# MezzanineDCDC_4646.net
KiCad netlist of a schematic drawn in Altium Designer
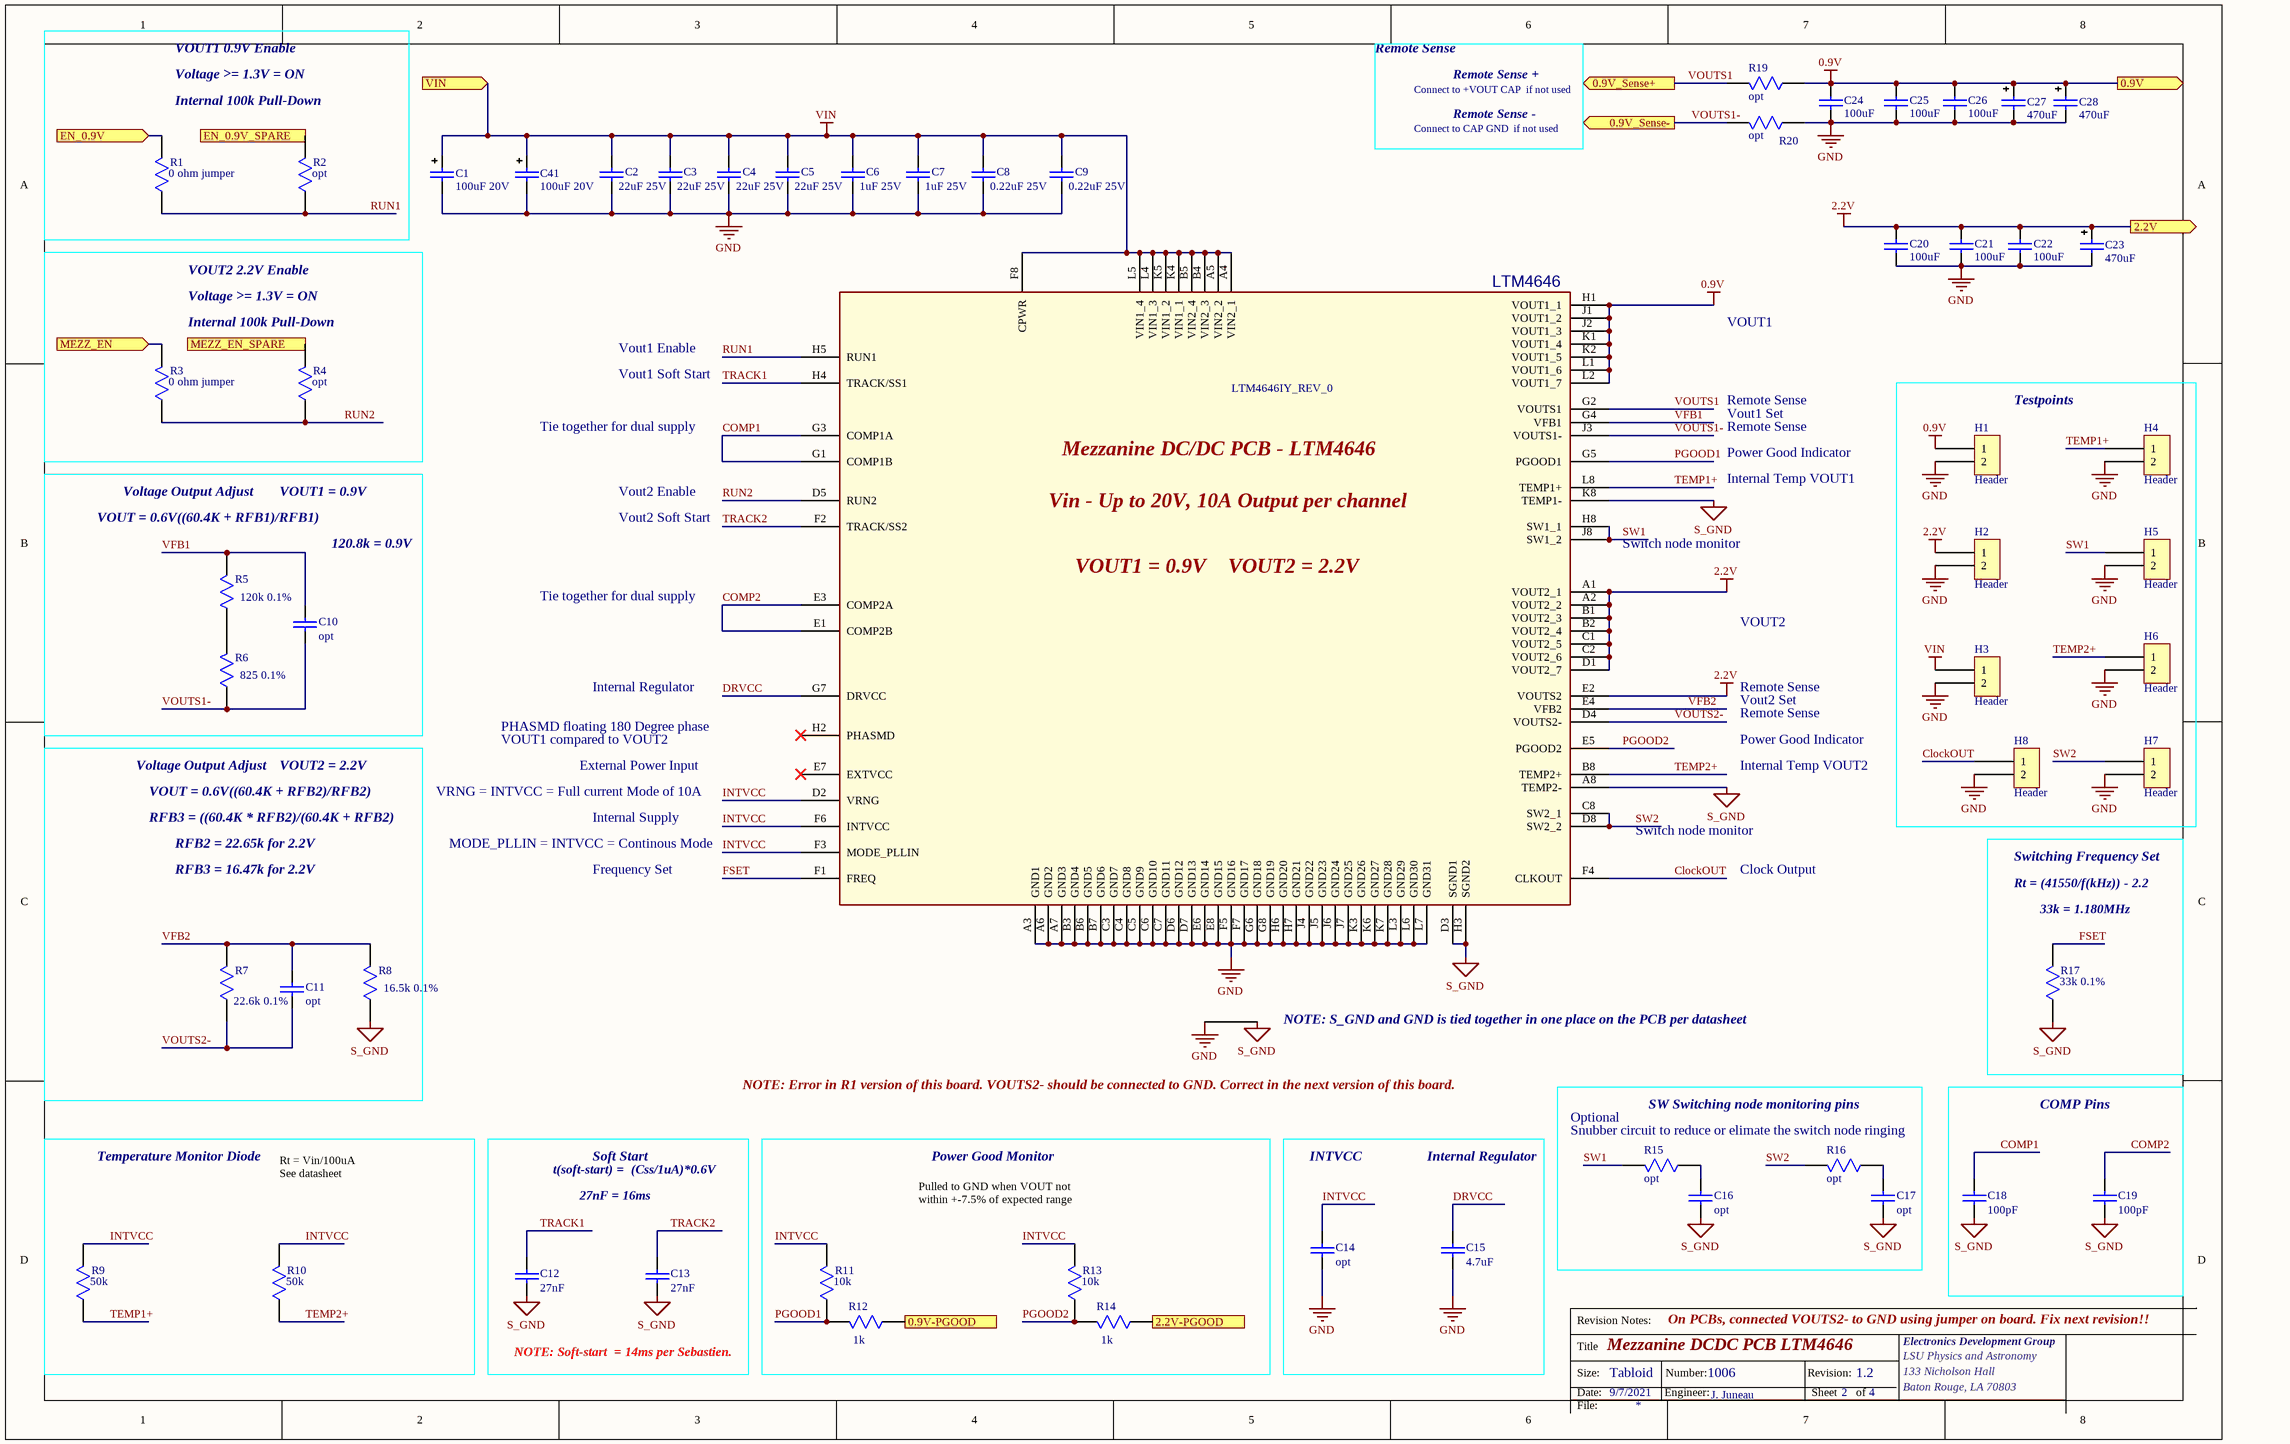
[diagram p0: MezzanineDCDC_4646.SchDoc]

(export (version "E")
  (design (tool "Eeschema 10.0.6"))
  (components
    (comp (ref "C1")
      (value "100uF 20V")
      (footprint "CAP 2917 Tantalum Polarized TAJE107K020RNJ")
      (description "100µF Molded Tantalum Capacitors 20V 2917 (7343 Metric) 400mOhm")
      (fields (field (name "Comment") "TAJE107K020RNJ"))
      (libsource (lib "MezzanineDCDC") (part "Capacitor 2917 TAJE107K020RNJ"))
    )
    (comp (ref "C2")
      (value "22uF 25V")
      (footprint "CAP 1210 Murata")
      (description "22µF ±10% 25V Ceramic Capacitor X5R 1210 (3225 Metric)")
      (fields (field (name "Comment") "GRM32ER61E226KE15L"))
      (libsource (lib "MezzanineDCDC") (part "Capacitor 1210"))
    )
    (comp (ref "C3")
      (value "22uF 25V")
      (footprint "CAP 1210 Murata")
      (description "22µF ±10% 25V Ceramic Capacitor X5R 1210 (3225 Metric)")
      (fields (field (name "Comment") "GRM32ER61E226KE15L"))
      (libsource (lib "MezzanineDCDC") (part "Capacitor 1210"))
    )
    (comp (ref "C4")
      (value "22uF 25V")
      (footprint "CAP 1210 Murata")
      (description "22µF ±10% 25V Ceramic Capacitor X5R 1210 (3225 Metric)")
      (fields (field (name "Comment") "GRM32ER61E226KE15L"))
      (libsource (lib "MezzanineDCDC") (part "Capacitor 1210"))
    )
    (comp (ref "C5")
      (value "22uF 25V")
      (footprint "CAP 1210 Murata")
      (description "22µF ±10% 25V Ceramic Capacitor X5R 1210 (3225 Metric)")
      (fields (field (name "Comment") "GRM32ER61E226KE15L"))
      (libsource (lib "MezzanineDCDC") (part "Capacitor 1210"))
    )
    (comp (ref "C6")
      (value "1uF 25V")
      (footprint "Cap 0603 TDK")
      (description "1µF ±10% 25V Ceramic Capacitor X7R 0603 (1608 Metric)")
      (fields (field (name "Comment") "GCM188R71E105KA64D"))
      (libsource (lib "MezzanineDCDC") (part "Capacitor 0603 TDK"))
    )
    (comp (ref "C7")
      (value "1uF 25V")
      (footprint "Cap 0603 TDK")
      (description "1µF ±10% 25V Ceramic Capacitor X7R 0603 (1608 Metric)")
      (fields (field (name "Comment") "GCM188R71E105KA64D"))
      (libsource (lib "MezzanineDCDC") (part "Capacitor 0603 TDK"))
    )
    (comp (ref "C8")
      (value "0.22uF 25V")
      (footprint "Cap 0603 TDK")
      (description "CAP CER 0.22UF 25V X7R 0603")
      (fields (field (name "Comment") "C1608X7R1E224K080AC"))
      (libsource (lib "MezzanineDCDC") (part "Capacitor 0603 TDK"))
    )
    (comp (ref "C9")
      (value "0.22uF 25V")
      (footprint "Cap 0603 TDK")
      (description "CAP CER 0.22UF 25V X7R 0603")
      (fields (field (name "Comment") "C1608X7R1E224K080AC"))
      (libsource (lib "MezzanineDCDC") (part "Capacitor 0603 TDK"))
    )
    (comp (ref "C10")
      (value "opt")
      (footprint "Cap 0603 TDK")
      (description "Capacitor 0603")
      (libsource (lib "MezzanineDCDC") (part "Capacitor 0603 TDK"))
    )
    (comp (ref "C11")
      (value "opt")
      (footprint "Cap 0603 TDK")
      (description "Capacitor 0603")
      (libsource (lib "MezzanineDCDC") (part "Capacitor 0603 TDK"))
    )
    (comp (ref "C12")
      (value "27nF")
      (footprint "Cap 0603 TDK")
      (description "0.027µF ±10% 16V Ceramic Capacitor X7R 0603 (1608 Metric)")
      (fields (field (name "Comment") "0603YC273KAT2A"))
      (libsource (lib "MezzanineDCDC") (part "Capacitor 0603 TDK"))
    )
    (comp (ref "C13")
      (value "27nF")
      (footprint "Cap 0603 TDK")
      (description "0.027µF ±10% 16V Ceramic Capacitor X7R 0603 (1608 Metric)")
      (fields (field (name "Comment") "0603YC273KAT2A"))
      (libsource (lib "MezzanineDCDC") (part "Capacitor 0603 TDK"))
    )
    (comp (ref "C14")
      (value "opt")
      (footprint "Cap 0603 TDK")
      (description "CAP CER 4.7UF 16V X5R 0603")
      (fields (field (name "Comment") "C1608X5R1C475K080AC"))
      (libsource (lib "MezzanineDCDC") (part "Capacitor 0603 TDK"))
    )
    (comp (ref "C15")
      (value "4.7uF")
      (footprint "Cap 0603 TDK")
      (description "CAP CER 4.7UF 16V X5R 0603")
      (fields (field (name "Comment") "C1608X5R1C475K080AC"))
      (libsource (lib "MezzanineDCDC") (part "Capacitor 0603 TDK"))
    )
    (comp (ref "C16")
      (value "opt")
      (footprint "Cap 0603 TDK")
      (description "Capacitor 0603")
      (libsource (lib "MezzanineDCDC") (part "Capacitor 0603 TDK"))
    )
    (comp (ref "C17")
      (value "opt")
      (footprint "Cap 0603 TDK")
      (description "Capacitor 0603")
      (libsource (lib "MezzanineDCDC") (part "Capacitor 0603 TDK"))
    )
    (comp (ref "C18")
      (value "100pF")
      (footprint "Cap 0603 TDK")
      (description "100pF ±10% 16V Ceramic Capacitor X7R 0603 (1608 Metric)")
      (fields (field (name "Comment") "0603YC101KAT2A"))
      (libsource (lib "MezzanineDCDC") (part "Capacitor 0603 TDK"))
    )
    (comp (ref "C19")
      (value "100pF")
      (footprint "Cap 0603 TDK")
      (description "100pF ±10% 16V Ceramic Capacitor X7R 0603 (1608 Metric)")
      (fields (field (name "Comment") "0603YC101KAT2A"))
      (libsource (lib "MezzanineDCDC") (part "Capacitor 0603 TDK"))
    )
    (comp (ref "C20")
      (value "100uF")
      (footprint "CAP 1210 Murata")
      (description "100µF ±20% 6.3V Ceramic Capacitor X5R 1210 (3225 Metric)")
      (fields (field (name "Comment") "GRM32ER60J107ME20K"))
      (libsource (lib "MezzanineDCDC") (part "Capacitor 1210"))
    )
    (comp (ref "C21")
      (value "100uF")
      (footprint "CAP 1210 Murata")
      (description "100µF ±20% 6.3V Ceramic Capacitor X5R 1210 (3225 Metric)")
      (fields (field (name "Comment") "GRM32ER60J107ME20K"))
      (libsource (lib "MezzanineDCDC") (part "Capacitor 1210"))
    )
    (comp (ref "C22")
      (value "100uF")
      (footprint "CAP 1210 Murata")
      (description "100µF ±20% 6.3V Ceramic Capacitor X5R 1210 (3225 Metric)")
      (fields (field (name "Comment") "GRM32ER60J107ME20K"))
      (libsource (lib "MezzanineDCDC") (part "Capacitor 1210"))
    )
    (comp (ref "C23")
      (value "470uF")
      (footprint "CAP 2917 Tantalum Polarized")
      (description "470µF Molded Tantalum Polymer Capacitor 4V 2917 (7343 Metric) 12mOhm @ 100kHz")
      (fields (field (name "Comment") "4TPE470MCL"))
      (libsource (lib "MezzanineDCDC") (part "Capacitor 2917 Panasonic"))
    )
    (comp (ref "C24")
      (value "100uF")
      (footprint "CAP 1210 Murata")
      (description "100µF ±20% 6.3V Ceramic Capacitor X5R 1210 (3225 Metric)")
      (fields (field (name "Comment") "GRM32ER60J107ME20K"))
      (libsource (lib "MezzanineDCDC") (part "Capacitor 1210"))
    )
    (comp (ref "C25")
      (value "100uF")
      (footprint "CAP 1210 Murata")
      (description "100µF ±20% 6.3V Ceramic Capacitor X5R 1210 (3225 Metric)")
      (fields (field (name "Comment") "GRM32ER60J107ME20K"))
      (libsource (lib "MezzanineDCDC") (part "Capacitor 1210"))
    )
    (comp (ref "C26")
      (value "100uF")
      (footprint "CAP 1210 Murata")
      (description "100µF ±20% 6.3V Ceramic Capacitor X5R 1210 (3225 Metric)")
      (fields (field (name "Comment") "GRM32ER60J107ME20K"))
      (libsource (lib "MezzanineDCDC") (part "Capacitor 1210"))
    )
    (comp (ref "C27")
      (value "470uF")
      (footprint "CAP 2917 Tantalum Polarized")
      (description "470µF Molded Tantalum Polymer Capacitor 4V 2917 (7343 Metric) 12mOhm @ 100kHz")
      (fields (field (name "Comment") "4TPE470MCL"))
      (libsource (lib "MezzanineDCDC") (part "Capacitor 2917 Panasonic"))
    )
    (comp (ref "C28")
      (value "470uF")
      (footprint "CAP 2917 Tantalum Polarized")
      (description "470µF Molded Tantalum Polymer Capacitor 4V 2917 (7343 Metric) 12mOhm @ 100kHz")
      (fields (field (name "Comment") "4TPE470MCL"))
      (libsource (lib "MezzanineDCDC") (part "Capacitor 2917 Panasonic"))
    )
    (comp (ref "C41")
      (value "100uF 20V")
      (footprint "CAP 2917 Tantalum Polarized TAJE107K020RNJ")
      (description "100µF Molded Tantalum Capacitors 20V 2917 (7343 Metric) 400mOhm")
      (fields (field (name "Comment") "TAJE107K020RNJ"))
      (libsource (lib "MezzanineDCDC") (part "Capacitor 2917 TAJE107K020RNJ"))
    )
    (comp (ref "H1")
      (value "Header")
      (footprint "Header 2Pin")
      (description "Connector Header Through Hole 2 position 0.100\" (2.54mm)")
      (libsource (lib "MezzanineDCDC") (part "Header - 2Pin"))
    )
    (comp (ref "H2")
      (value "Header")
      (footprint "Header 2Pin")
      (description "Connector Header Through Hole 2 position 0.100\" (2.54mm)")
      (libsource (lib "MezzanineDCDC") (part "Header - 2Pin"))
    )
    (comp (ref "H3")
      (value "Header")
      (footprint "Header 2Pin")
      (description "Connector Header Through Hole 2 position 0.100\" (2.54mm)")
      (libsource (lib "MezzanineDCDC") (part "Header - 2Pin"))
    )
    (comp (ref "H4")
      (value "Header")
      (footprint "Header 2Pin")
      (description "Connector Header Through Hole 2 position 0.100\" (2.54mm)")
      (libsource (lib "MezzanineDCDC") (part "Header - 2Pin"))
    )
    (comp (ref "H5")
      (value "Header")
      (footprint "Header 2Pin")
      (description "Connector Header Through Hole 2 position 0.100\" (2.54mm)")
      (libsource (lib "MezzanineDCDC") (part "Header - 2Pin"))
    )
    (comp (ref "H6")
      (value "Header")
      (footprint "Header 2Pin")
      (description "Connector Header Through Hole 2 position 0.100\" (2.54mm)")
      (libsource (lib "MezzanineDCDC") (part "Header - 2Pin"))
    )
    (comp (ref "H7")
      (value "Header")
      (footprint "Header 2Pin")
      (description "Connector Header Through Hole 2 position 0.100\" (2.54mm)")
      (libsource (lib "MezzanineDCDC") (part "Header - 2Pin"))
    )
    (comp (ref "H8")
      (value "Header")
      (footprint "Header 2Pin")
      (description "Connector Header Through Hole 2 position 0.100\" (2.54mm)")
      (libsource (lib "MezzanineDCDC") (part "Header - 2Pin"))
    )
    (comp (ref "R1")
      (value "0 ohm jumper")
      (footprint "Resistor ERJ2G/CRCW 0402")
      (description "Jumper 0.063W, 1/16W Chip Resistor 0402 (1005 Metric) Automotive AEC-Q200 Thick Film")
      (fields (field (name "Comment") "CRCW04020000ZSTD"))
      (libsource (lib "MezzanineDCDC") (part "ERJ2G Resistor 0402"))
    )
    (comp (ref "R2")
      (value "opt")
      (footprint "Resistor ERJ2G/CRCW 0402")
      (description "Resistor 0402")
      (libsource (lib "MezzanineDCDC") (part "ERJ2G Resistor 0402"))
    )
    (comp (ref "R3")
      (value "0 ohm jumper")
      (footprint "Resistor ERJ2G/CRCW 0402")
      (description "Jumper 0.063W, 1/16W Chip Resistor 0402 (1005 Metric) Automotive AEC-Q200 Thick Film")
      (fields (field (name "Comment") "CRCW04020000ZSTD"))
      (libsource (lib "MezzanineDCDC") (part "ERJ2G Resistor 0402"))
    )
    (comp (ref "R4")
      (value "opt")
      (footprint "Resistor ERJ2G/CRCW 0402")
      (description "Resistor 0402")
      (libsource (lib "MezzanineDCDC") (part "ERJ2G Resistor 0402"))
    )
    (comp (ref "R5")
      (value "120k 0.1%")
      (footprint "Resistor 0603 - ERJ")
      (description "120 kOhms ±0.1% 0.1W, 1/10W Chip Resistor 0603 (1608 Metric) Automotive AEC-Q200 Thin Film")
      (fields (field (name "Comment") "ERA-3AEB124V"))
      (libsource (lib "MezzanineDCDC") (part "Resistor 0603"))
    )
    (comp (ref "R6")
      (value "825 0.1%")
      (footprint "Resistor 0603 - ERJ")
      (description "RES SMD 825 OHM 0.1% 1/10W 0603")
      (fields (field (name "Comment") "ERA-3AEB8250V"))
      (libsource (lib "MezzanineDCDC") (part "Resistor 0603"))
    )
    (comp (ref "R7")
      (value "22.6k 0.1%")
      (footprint "Resistor 0603 - ERJ")
      (description "22.6 kOhms ±0.1% 0.1W, 1/10W Chip Resistor 0603 (1608 Metric) Automotive AEC-Q200 Thin Film")
      (fields (field (name "Comment") "ERA-3AEB2262V"))
      (libsource (lib "MezzanineDCDC") (part "Resistor 0603"))
    )
    (comp (ref "R8")
      (value "16.5k 0.1%")
      (footprint "Resistor 0603 - ERJ")
      (description "16.5 kOhms ±0.1% 0.1W, 1/10W Chip Resistor 0603 (1608 Metric) Automotive AEC-Q200 Thin Film")
      (fields (field (name "Comment") "ERA-3AEB1652V"))
      (libsource (lib "MezzanineDCDC") (part "Resistor 0603"))
    )
    (comp (ref "R9")
      (value "50k")
      (footprint "Resistor ERJ2G/CRCW 0402")
      (description "49.9 ±0.1% 0.063W, 1/16W Chip Resistor 0402 (1005 Metric) Automotive AEC-Q200 Thin Film")
      (fields (field (name "Comment") "ERA-2AEB4992X"))
      (libsource (lib "MezzanineDCDC") (part "ERJ2G Resistor 0402"))
    )
    (comp (ref "R10")
      (value "50k")
      (footprint "Resistor ERJ2G/CRCW 0402")
      (description "49.9 ±0.1% 0.063W, 1/16W Chip Resistor 0402 (1005 Metric) Automotive AEC-Q200 Thin Film")
      (fields (field (name "Comment") "ERA-2AEB4992X"))
      (libsource (lib "MezzanineDCDC") (part "ERJ2G Resistor 0402"))
    )
    (comp (ref "R11")
      (value "10k")
      (footprint "Resistor ERJ2G/CRCW 0402")
      (description "RES SMD 10K OHM 5% 1/10W 0402")
      (fields (field (name "Comment") "ERJ-2GEJ103X"))
      (libsource (lib "MezzanineDCDC") (part "ERJ2G Resistor 0402"))
    )
    (comp (ref "R12")
      (value "1k")
      (footprint "Resistor ERJ2G/CRCW 0402")
      (description "RES SMD 1K OHM 5% 1/10W 0402")
      (fields (field (name "Comment") "ERJ-2GEJ102X"))
      (libsource (lib "MezzanineDCDC") (part "ERJ2G Resistor 0402"))
    )
    (comp (ref "R13")
      (value "10k")
      (footprint "Resistor ERJ2G/CRCW 0402")
      (description "RES SMD 10K OHM 5% 1/10W 0402")
      (fields (field (name "Comment") "ERJ-2GEJ103X"))
      (libsource (lib "MezzanineDCDC") (part "ERJ2G Resistor 0402"))
    )
    (comp (ref "R14")
      (value "1k")
      (footprint "Resistor ERJ2G/CRCW 0402")
      (description "RES SMD 1K OHM 5% 1/10W 0402")
      (fields (field (name "Comment") "ERJ-2GEJ102X"))
      (libsource (lib "MezzanineDCDC") (part "ERJ2G Resistor 0402"))
    )
    (comp (ref "R15")
      (value "opt")
      (footprint "Resistor ERJ2G/CRCW 0402")
      (description "Resistor 0402")
      (libsource (lib "MezzanineDCDC") (part "ERJ2G Resistor 0402"))
    )
    (comp (ref "R16")
      (value "opt")
      (footprint "Resistor ERJ2G/CRCW 0402")
      (description "Resistor 0402")
      (libsource (lib "MezzanineDCDC") (part "ERJ2G Resistor 0402"))
    )
    (comp (ref "R17")
      (value "33k 0.1%")
      (footprint "Resistor 0603 - ERJ")
      (description "33 ±0.1% 0.1W, 1/10W Chip Resistor 0603 (1608 Metric) Automotive AEC-Q200 Thin Film")
      (fields (field (name "Comment") "ERA-3AEB333V"))
      (libsource (lib "MezzanineDCDC") (part "Resistor 0603"))
    )
    (comp (ref "R19")
      (value "opt")
      (footprint "Resistor ERJ2G/CRCW 0402")
      (description "Resistor 0402")
      (libsource (lib "MezzanineDCDC") (part "ERJ2G Resistor 0402"))
    )
    (comp (ref "R20")
      (value "opt")
      (footprint "Resistor ERJ2G/CRCW 0402")
      (description "Resistor 0402")
      (libsource (lib "MezzanineDCDC") (part "ERJ2G Resistor 0402"))
    )
    (comp (ref "U1")
      (value "LTM4646IY_REV_0")
      (footprint "LTM4646")
      (libsource (lib "MezzanineDCDC") (part "LTM4646IY 05-11-0399"))
    )
  )
  (nets
    (net (code "1") (name "/0.9V-PGOOD") (class "Default")
      (node (ref "R12") (pin "1") (pinfunction "0_1") (pintype "passive"))
    )
    (net (code "2") (name "/2.2V-PGOOD") (class "Default")
      (node (ref "R14") (pin "1") (pinfunction "0_1") (pintype "passive"))
    )
    (net (code "3") (name "/COMP1") (class "Default")
      (node (ref "C18") (pin "1") (pinfunction "1_1") (pintype "passive"))
      (node (ref "U1") (pin "G1") (pinfunction "COMP1B_G1") (pintype "passive"))
      (node (ref "U1") (pin "G3") (pinfunction "COMP1A_G3") (pintype "passive"))
    )
    (net (code "4") (name "/COMP2") (class "Default")
      (node (ref "C19") (pin "1") (pinfunction "1_1") (pintype "passive"))
      (node (ref "U1") (pin "E1") (pinfunction "COMP2B_E1") (pintype "passive"))
      (node (ref "U1") (pin "E3") (pinfunction "COMP2A_E3") (pintype "passive"))
    )
    (net (code "5") (name "/ClockOUT") (class "Default")
      (node (ref "H8") (pin "1") (pinfunction "1_1") (pintype "passive"))
      (node (ref "U1") (pin "F4") (pinfunction "CLKOUT_F4") (pintype "passive"))
    )
    (net (code "6") (name "/DRVCC") (class "Default")
      (node (ref "C15") (pin "1") (pinfunction "1_1") (pintype "passive"))
      (node (ref "U1") (pin "G7") (pinfunction "DRVCC_G7") (pintype "passive"))
    )
    (net (code "7") (name "/EN_0.9V") (class "Default")
      (node (ref "R1") (pin "2") (pinfunction "1_2") (pintype "passive"))
    )
    (net (code "8") (name "/EN_0.9V_SPARE") (class "Default")
      (node (ref "R2") (pin "2") (pinfunction "1_2") (pintype "passive"))
    )
    (net (code "9") (name "/FSET") (class "Default")
      (node (ref "R17") (pin "2") (pinfunction "1_2") (pintype "passive"))
      (node (ref "U1") (pin "F1") (pinfunction "FREQ_F1") (pintype "passive"))
    )
    (net (code "10") (name "/INTVCC") (class "Default")
      (node (ref "C14") (pin "1") (pinfunction "1_1") (pintype "passive"))
      (node (ref "R10") (pin "2") (pinfunction "1_2") (pintype "passive"))
      (node (ref "R11") (pin "2") (pinfunction "1_2") (pintype "passive"))
      (node (ref "R13") (pin "2") (pinfunction "1_2") (pintype "passive"))
      (node (ref "R9") (pin "2") (pinfunction "1_2") (pintype "passive"))
      (node (ref "U1") (pin "D2") (pinfunction "VRNG_D2") (pintype "passive"))
      (node (ref "U1") (pin "F3") (pinfunction "MODE_PLLIN_F3") (pintype "passive"))
      (node (ref "U1") (pin "F6") (pinfunction "INTVCC_F6") (pintype "passive"))
    )
    (net (code "11") (name "/MEZZ_EN") (class "Default")
      (node (ref "R3") (pin "2") (pinfunction "1_2") (pintype "passive"))
    )
    (net (code "12") (name "/MEZZ_EN_SPARE") (class "Default")
      (node (ref "R4") (pin "2") (pinfunction "1_2") (pintype "passive"))
    )
    (net (code "13") (name "/PGOOD1") (class "Default")
      (node (ref "R11") (pin "1") (pinfunction "0_1") (pintype "passive"))
      (node (ref "R12") (pin "2") (pinfunction "1_2") (pintype "passive"))
      (node (ref "U1") (pin "G5") (pinfunction "PGOOD1_G5") (pintype "passive"))
    )
    (net (code "14") (name "/PGOOD2") (class "Default")
      (node (ref "R13") (pin "1") (pinfunction "0_1") (pintype "passive"))
      (node (ref "R14") (pin "2") (pinfunction "1_2") (pintype "passive"))
      (node (ref "U1") (pin "E5") (pinfunction "PGOOD2_E5") (pintype "passive"))
    )
    (net (code "15") (name "/RUN1") (class "Default")
      (node (ref "R1") (pin "1") (pinfunction "0_1") (pintype "passive"))
      (node (ref "R2") (pin "1") (pinfunction "0_1") (pintype "passive"))
      (node (ref "U1") (pin "H5") (pinfunction "RUN1_H5") (pintype "passive"))
    )
    (net (code "16") (name "/RUN2") (class "Default")
      (node (ref "R3") (pin "1") (pinfunction "0_1") (pintype "passive"))
      (node (ref "R4") (pin "1") (pinfunction "0_1") (pintype "passive"))
      (node (ref "U1") (pin "D5") (pinfunction "RUN2_D5") (pintype "passive"))
    )
    (net (code "17") (name "/SW1") (class "Default")
      (node (ref "H5") (pin "1") (pinfunction "1_1") (pintype "passive"))
      (node (ref "R15") (pin "2") (pinfunction "1_2") (pintype "passive"))
      (node (ref "U1") (pin "H8") (pinfunction "SW1_1_H8") (pintype "passive"))
      (node (ref "U1") (pin "J8") (pinfunction "SW1_2_J8") (pintype "passive"))
    )
    (net (code "18") (name "/SW2") (class "Default")
      (node (ref "H7") (pin "1") (pinfunction "1_1") (pintype "passive"))
      (node (ref "R16") (pin "2") (pinfunction "1_2") (pintype "passive"))
      (node (ref "U1") (pin "C8") (pinfunction "SW2_1_C8") (pintype "passive"))
      (node (ref "U1") (pin "D8") (pinfunction "SW2_2_D8") (pintype "passive"))
    )
    (net (code "19") (name "/TEMP1+") (class "Default")
      (node (ref "H4") (pin "1") (pinfunction "1_1") (pintype "passive"))
      (node (ref "R9") (pin "1") (pinfunction "0_1") (pintype "passive"))
      (node (ref "U1") (pin "L8") (pinfunction "TEMP1+_L8") (pintype "passive"))
    )
    (net (code "20") (name "/TEMP2+") (class "Default")
      (node (ref "H6") (pin "1") (pinfunction "1_1") (pintype "passive"))
      (node (ref "R10") (pin "1") (pinfunction "0_1") (pintype "passive"))
      (node (ref "U1") (pin "B8") (pinfunction "TEMP2+_B8") (pintype "passive"))
    )
    (net (code "21") (name "/TRACK1") (class "Default")
      (node (ref "C12") (pin "1") (pinfunction "1_1") (pintype "passive"))
      (node (ref "U1") (pin "H4") (pinfunction "TRACK/SS1_H4") (pintype "passive"))
    )
    (net (code "22") (name "/TRACK2") (class "Default")
      (node (ref "C13") (pin "1") (pinfunction "1_1") (pintype "passive"))
      (node (ref "U1") (pin "F2") (pinfunction "TRACK/SS2_F2") (pintype "passive"))
    )
    (net (code "23") (name "/VFB1") (class "Default")
      (node (ref "C10") (pin "1") (pinfunction "1_1") (pintype "passive"))
      (node (ref "R5") (pin "2") (pinfunction "1_2") (pintype "passive"))
      (node (ref "U1") (pin "G4") (pinfunction "VFB1_G4") (pintype "passive"))
    )
    (net (code "24") (name "/VFB2") (class "Default")
      (node (ref "C11") (pin "1") (pinfunction "1_1") (pintype "passive"))
      (node (ref "R7") (pin "2") (pinfunction "1_2") (pintype "passive"))
      (node (ref "R8") (pin "2") (pinfunction "1_2") (pintype "passive"))
      (node (ref "U1") (pin "E4") (pinfunction "VFB2_E4") (pintype "passive"))
    )
    (net (code "25") (name "/VOUTS1") (class "Default")
      (node (ref "R19") (pin "2") (pinfunction "1_2") (pintype "passive"))
      (node (ref "U1") (pin "G2") (pinfunction "VOUTS1_G2") (pintype "passive"))
    )
    (net (code "26") (name "/VOUTS1-") (class "Default")
      (node (ref "C10") (pin "2") (pinfunction "2_2") (pintype "passive"))
      (node (ref "R20") (pin "2") (pinfunction "1_2") (pintype "passive"))
      (node (ref "R6") (pin "1") (pinfunction "0_1") (pintype "passive"))
      (node (ref "U1") (pin "J3") (pinfunction "VOUTS1-_J3") (pintype "passive"))
    )
    (net (code "27") (name "/VOUTS2-") (class "Default")
      (node (ref "C11") (pin "2") (pinfunction "2_2") (pintype "passive"))
      (node (ref "R7") (pin "1") (pinfunction "0_1") (pintype "passive"))
      (node (ref "U1") (pin "D4") (pinfunction "VOUTS2-_D4") (pintype "passive"))
    )
    (net (code "28") (name "0.9V") (class "Default")
      (node (ref "C24") (pin "1") (pinfunction "1_1") (pintype "passive"))
      (node (ref "C25") (pin "1") (pinfunction "1_1") (pintype "passive"))
      (node (ref "C26") (pin "1") (pinfunction "1_1") (pintype "passive"))
      (node (ref "C27") (pin "1") (pinfunction "1_1") (pintype "passive"))
      (node (ref "C28") (pin "1") (pinfunction "1_1") (pintype "passive"))
      (node (ref "H1") (pin "1") (pinfunction "1_1") (pintype "passive"))
      (node (ref "R19") (pin "1") (pinfunction "0_1") (pintype "passive"))
      (node (ref "U1") (pin "H1") (pinfunction "VOUT1_1_H1") (pintype "passive"))
      (node (ref "U1") (pin "J1") (pinfunction "VOUT1_2_J1") (pintype "passive"))
      (node (ref "U1") (pin "J2") (pinfunction "VOUT1_3_J2") (pintype "passive"))
      (node (ref "U1") (pin "K1") (pinfunction "VOUT1_4_K1") (pintype "passive"))
      (node (ref "U1") (pin "K2") (pinfunction "VOUT1_5_K2") (pintype "passive"))
      (node (ref "U1") (pin "L1") (pinfunction "VOUT1_6_L1") (pintype "passive"))
      (node (ref "U1") (pin "L2") (pinfunction "VOUT1_7_L2") (pintype "passive"))
    )
    (net (code "29") (name "2.2V") (class "Default")
      (node (ref "C20") (pin "1") (pinfunction "1_1") (pintype "passive"))
      (node (ref "C21") (pin "1") (pinfunction "1_1") (pintype "passive"))
      (node (ref "C22") (pin "1") (pinfunction "1_1") (pintype "passive"))
      (node (ref "C23") (pin "1") (pinfunction "1_1") (pintype "passive"))
      (node (ref "H2") (pin "1") (pinfunction "1_1") (pintype "passive"))
      (node (ref "U1") (pin "A1") (pinfunction "VOUT2_1_A1") (pintype "passive"))
      (node (ref "U1") (pin "A2") (pinfunction "VOUT2_2_A2") (pintype "passive"))
      (node (ref "U1") (pin "B1") (pinfunction "VOUT2_3_B1") (pintype "passive"))
      (node (ref "U1") (pin "B2") (pinfunction "VOUT2_4_B2") (pintype "passive"))
      (node (ref "U1") (pin "C1") (pinfunction "VOUT2_5_C1") (pintype "passive"))
      (node (ref "U1") (pin "C2") (pinfunction "VOUT2_6_C2") (pintype "passive"))
      (node (ref "U1") (pin "D1") (pinfunction "VOUT2_7_D1") (pintype "passive"))
      (node (ref "U1") (pin "E2") (pinfunction "VOUTS2_E2") (pintype "passive"))
    )
    (net (code "30") (name "GND") (class "Default")
      (node (ref "C1") (pin "2") (pinfunction "2_2") (pintype "passive"))
      (node (ref "C14") (pin "2") (pinfunction "2_2") (pintype "passive"))
      (node (ref "C15") (pin "2") (pinfunction "2_2") (pintype "passive"))
      (node (ref "C2") (pin "2") (pinfunction "2_2") (pintype "passive"))
      (node (ref "C20") (pin "2") (pinfunction "2_2") (pintype "passive"))
      (node (ref "C21") (pin "2") (pinfunction "2_2") (pintype "passive"))
      (node (ref "C22") (pin "2") (pinfunction "2_2") (pintype "passive"))
      (node (ref "C23") (pin "2") (pinfunction "2_2") (pintype "passive"))
      (node (ref "C24") (pin "2") (pinfunction "2_2") (pintype "passive"))
      (node (ref "C25") (pin "2") (pinfunction "2_2") (pintype "passive"))
      (node (ref "C26") (pin "2") (pinfunction "2_2") (pintype "passive"))
      (node (ref "C27") (pin "2") (pinfunction "2_2") (pintype "passive"))
      (node (ref "C28") (pin "2") (pinfunction "2_2") (pintype "passive"))
      (node (ref "C3") (pin "2") (pinfunction "2_2") (pintype "passive"))
      (node (ref "C4") (pin "2") (pinfunction "2_2") (pintype "passive"))
      (node (ref "C41") (pin "2") (pinfunction "2_2") (pintype "passive"))
      (node (ref "C5") (pin "2") (pinfunction "2_2") (pintype "passive"))
      (node (ref "C6") (pin "2") (pinfunction "2_2") (pintype "passive"))
      (node (ref "C7") (pin "2") (pinfunction "2_2") (pintype "passive"))
      (node (ref "C8") (pin "2") (pinfunction "2_2") (pintype "passive"))
      (node (ref "C9") (pin "2") (pinfunction "2_2") (pintype "passive"))
      (node (ref "H1") (pin "2") (pinfunction "2_2") (pintype "passive"))
      (node (ref "H2") (pin "2") (pinfunction "2_2") (pintype "passive"))
      (node (ref "H3") (pin "2") (pinfunction "2_2") (pintype "passive"))
      (node (ref "H4") (pin "2") (pinfunction "2_2") (pintype "passive"))
      (node (ref "H5") (pin "2") (pinfunction "2_2") (pintype "passive"))
      (node (ref "H6") (pin "2") (pinfunction "2_2") (pintype "passive"))
      (node (ref "H7") (pin "2") (pinfunction "2_2") (pintype "passive"))
      (node (ref "H8") (pin "2") (pinfunction "2_2") (pintype "passive"))
      (node (ref "R20") (pin "1") (pinfunction "0_1") (pintype "passive"))
      (node (ref "U1") (pin "A3") (pinfunction "GND1_A3") (pintype "passive"))
      (node (ref "U1") (pin "A6") (pinfunction "GND2_A6") (pintype "passive"))
      (node (ref "U1") (pin "A7") (pinfunction "GND3_A7") (pintype "passive"))
      (node (ref "U1") (pin "B3") (pinfunction "GND4_B3") (pintype "passive"))
      (node (ref "U1") (pin "B6") (pinfunction "GND5_B6") (pintype "passive"))
      (node (ref "U1") (pin "B7") (pinfunction "GND6_B7") (pintype "passive"))
      (node (ref "U1") (pin "C3") (pinfunction "GND7_C3") (pintype "passive"))
      (node (ref "U1") (pin "C4") (pinfunction "GND8_C4") (pintype "passive"))
      (node (ref "U1") (pin "C5") (pinfunction "GND9_C5") (pintype "passive"))
      (node (ref "U1") (pin "C6") (pinfunction "GND10_C6") (pintype "passive"))
      (node (ref "U1") (pin "C7") (pinfunction "GND11_C7") (pintype "passive"))
      (node (ref "U1") (pin "D6") (pinfunction "GND12_D6") (pintype "passive"))
      (node (ref "U1") (pin "D7") (pinfunction "GND13_D7") (pintype "passive"))
      (node (ref "U1") (pin "E6") (pinfunction "GND14_E6") (pintype "passive"))
      (node (ref "U1") (pin "E8") (pinfunction "GND15_E8") (pintype "passive"))
      (node (ref "U1") (pin "F5") (pinfunction "GND16_F5") (pintype "passive"))
      (node (ref "U1") (pin "F7") (pinfunction "GND17_F7") (pintype "passive"))
      (node (ref "U1") (pin "G6") (pinfunction "GND18_G6") (pintype "passive"))
      (node (ref "U1") (pin "G8") (pinfunction "GND19_G8") (pintype "passive"))
      (node (ref "U1") (pin "H6") (pinfunction "GND20_H6") (pintype "passive"))
      (node (ref "U1") (pin "H7") (pinfunction "GND21_H7") (pintype "passive"))
      (node (ref "U1") (pin "J4") (pinfunction "GND22_J4") (pintype "passive"))
      (node (ref "U1") (pin "J5") (pinfunction "GND23_J5") (pintype "passive"))
      (node (ref "U1") (pin "J6") (pinfunction "GND24_J6") (pintype "passive"))
      (node (ref "U1") (pin "J7") (pinfunction "GND25_J7") (pintype "passive"))
      (node (ref "U1") (pin "K3") (pinfunction "GND26_K3") (pintype "passive"))
      (node (ref "U1") (pin "K6") (pinfunction "GND27_K6") (pintype "passive"))
      (node (ref "U1") (pin "K7") (pinfunction "GND28_K7") (pintype "passive"))
      (node (ref "U1") (pin "L3") (pinfunction "GND29_L3") (pintype "passive"))
      (node (ref "U1") (pin "L6") (pinfunction "GND30_L6") (pintype "passive"))
      (node (ref "U1") (pin "L7") (pinfunction "GND31_L7") (pintype "passive"))
    )
    (net (code "31") (name "Net-(R5-0)") (class "Default")
      (node (ref "R5") (pin "1") (pinfunction "0_1") (pintype "passive"))
      (node (ref "R6") (pin "2") (pinfunction "1_2") (pintype "passive"))
    )
    (net (code "32") (name "Net-(R15-0)") (class "Default")
      (node (ref "C16") (pin "1") (pinfunction "1_1") (pintype "passive"))
      (node (ref "R15") (pin "1") (pinfunction "0_1") (pintype "passive"))
    )
    (net (code "33") (name "Net-(R16-0)") (class "Default")
      (node (ref "C17") (pin "1") (pinfunction "1_1") (pintype "passive"))
      (node (ref "R16") (pin "1") (pinfunction "0_1") (pintype "passive"))
    )
    (net (code "34") (name "S_GND") (class "Default")
      (node (ref "C12") (pin "2") (pinfunction "2_2") (pintype "passive"))
      (node (ref "C13") (pin "2") (pinfunction "2_2") (pintype "passive"))
      (node (ref "C16") (pin "2") (pinfunction "2_2") (pintype "passive"))
      (node (ref "C17") (pin "2") (pinfunction "2_2") (pintype "passive"))
      (node (ref "C18") (pin "2") (pinfunction "2_2") (pintype "passive"))
      (node (ref "C19") (pin "2") (pinfunction "2_2") (pintype "passive"))
      (node (ref "R17") (pin "1") (pinfunction "0_1") (pintype "passive"))
      (node (ref "R8") (pin "1") (pinfunction "0_1") (pintype "passive"))
      (node (ref "U1") (pin "A8") (pinfunction "TEMP2-_A8") (pintype "passive"))
      (node (ref "U1") (pin "D3") (pinfunction "SGND1_D3") (pintype "passive"))
      (node (ref "U1") (pin "H3") (pinfunction "SGND2_H3") (pintype "passive"))
      (node (ref "U1") (pin "K8") (pinfunction "TEMP1-_K8") (pintype "passive"))
    )
    (net (code "35") (name "VIN") (class "Default")
      (node (ref "C1") (pin "1") (pinfunction "1_1") (pintype "passive"))
      (node (ref "C2") (pin "1") (pinfunction "1_1") (pintype "passive"))
      (node (ref "C3") (pin "1") (pinfunction "1_1") (pintype "passive"))
      (node (ref "C4") (pin "1") (pinfunction "1_1") (pintype "passive"))
      (node (ref "C41") (pin "1") (pinfunction "1_1") (pintype "passive"))
      (node (ref "C5") (pin "1") (pinfunction "1_1") (pintype "passive"))
      (node (ref "C6") (pin "1") (pinfunction "1_1") (pintype "passive"))
      (node (ref "C7") (pin "1") (pinfunction "1_1") (pintype "passive"))
      (node (ref "C8") (pin "1") (pinfunction "1_1") (pintype "passive"))
      (node (ref "C9") (pin "1") (pinfunction "1_1") (pintype "passive"))
      (node (ref "H3") (pin "1") (pinfunction "1_1") (pintype "passive"))
      (node (ref "U1") (pin "A4") (pinfunction "VIN2_1_A4") (pintype "passive"))
      (node (ref "U1") (pin "A5") (pinfunction "VIN2_2_A5") (pintype "passive"))
      (node (ref "U1") (pin "B4") (pinfunction "VIN2_3_B4") (pintype "passive"))
      (node (ref "U1") (pin "B5") (pinfunction "VIN2_4_B5") (pintype "passive"))
      (node (ref "U1") (pin "F8") (pinfunction "CPWR_F8") (pintype "passive"))
      (node (ref "U1") (pin "K4") (pinfunction "VIN1_1_K4") (pintype "passive"))
      (node (ref "U1") (pin "K5") (pinfunction "VIN1_2_K5") (pintype "passive"))
      (node (ref "U1") (pin "L4") (pinfunction "VIN1_3_L4") (pintype "passive"))
      (node (ref "U1") (pin "L5") (pinfunction "VIN1_4_L5") (pintype "passive"))
    )
    (net (code "36") (name "unconnected-(U1-EXTVCC-PadE7)") (class "Default")
      (node (ref "U1") (pin "E7") (pinfunction "EXTVCC_E7") (pintype "passive+no_connect"))
    )
    (net (code "37") (name "unconnected-(U1-PHASMD-PadH2)") (class "Default")
      (node (ref "U1") (pin "H2") (pinfunction "PHASMD_H2") (pintype "passive+no_connect"))
    )
  )
)
